# PMU.net
KiCad netlist of a schematic drawn in Altium Designer
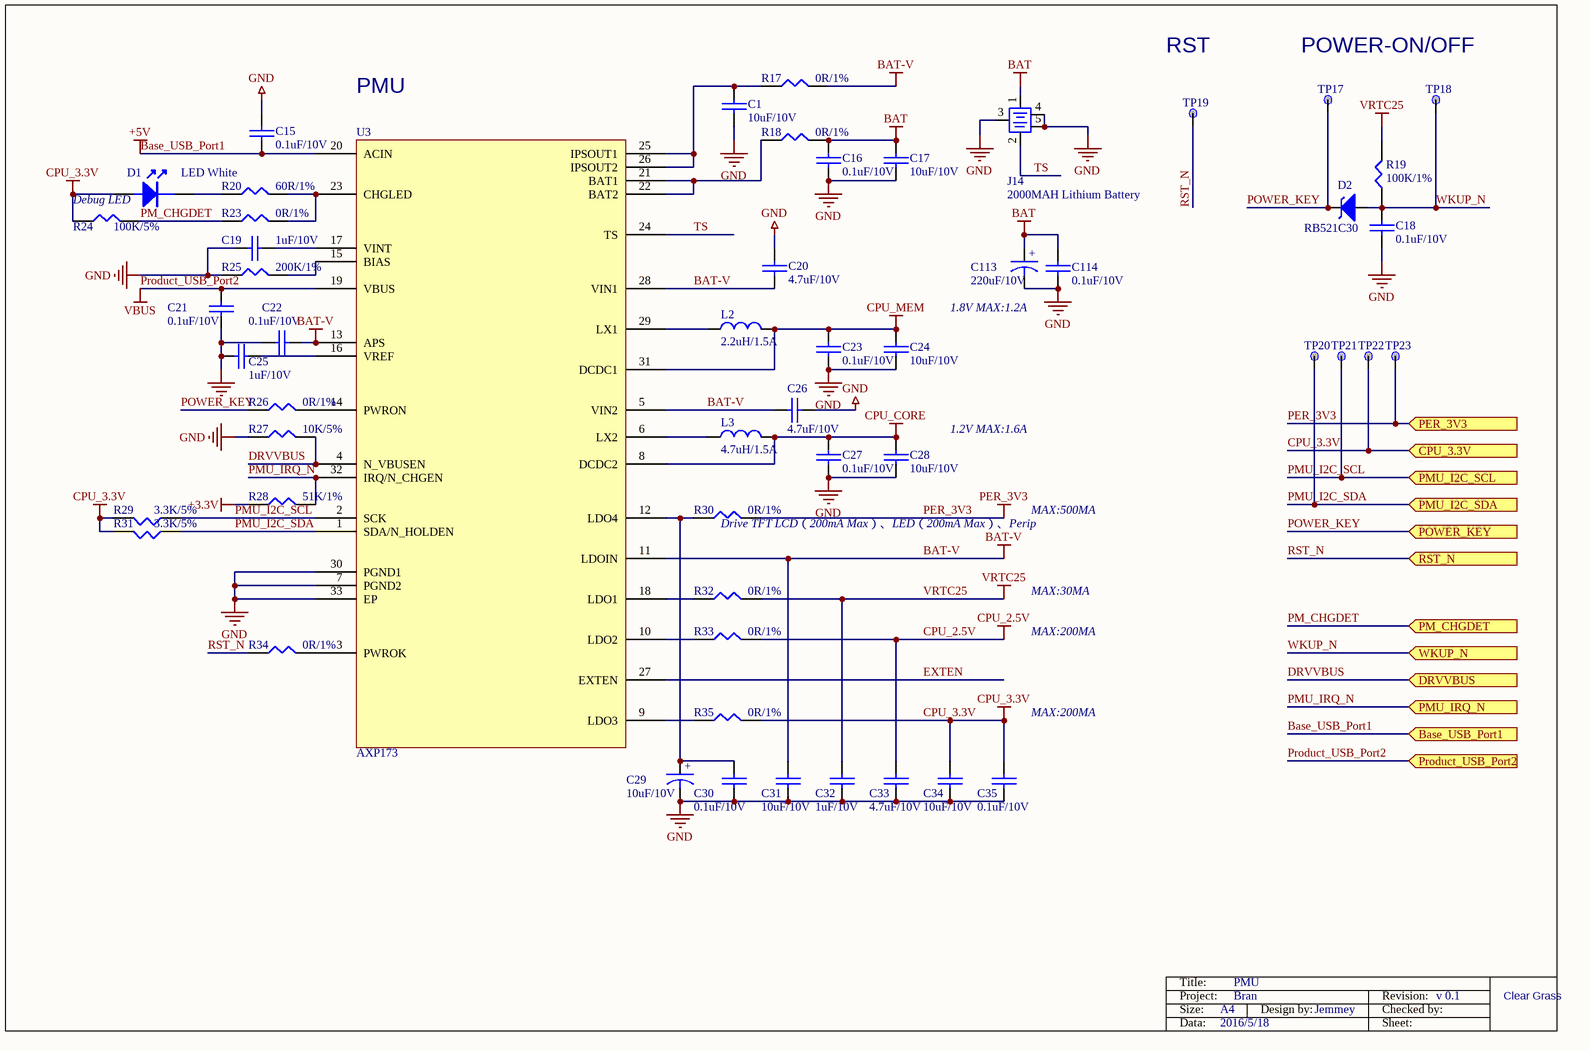
[diagram p0: PMU.SchDoc]

(export (version "E")
  (design (tool "Eeschema 10.0.6"))
  (components
    (comp (ref "C1")
      (value "10uF/10V")
      (footprint "0402C")
      (description "厂家：Murata，型号：GRM155R71A104KA01D")
      (libsource (lib "*") (part "CAP"))
    )
    (comp (ref "C15")
      (value "0.1uF/10V")
      (footprint "0402C")
      (description "厂家：Murata，型号：GRM155R71A104KA01D")
      (libsource (lib "*") (part "CAP"))
    )
    (comp (ref "C16")
      (value "0.1uF/10V")
      (footprint "0402C")
      (description "厂家：Murata，型号：GRM155R71A104KA01D")
      (libsource (lib "*") (part "CAP"))
    )
    (comp (ref "C17")
      (value "10uF/10V")
      (footprint "0402C")
      (description "厂家：Murata，型号：GRM155R71A104KA01D")
      (libsource (lib "*") (part "CAP"))
    )
    (comp (ref "C18")
      (value "0.1uF/10V")
      (footprint "0402C")
      (description "厂家：Murata，型号：GRM155R71A104KA01D")
      (libsource (lib "*") (part "CAP"))
    )
    (comp (ref "C19")
      (value "1uF/10V")
      (footprint "0402C")
      (description "厂家：Murata，型号：GRM155R71A104KA01D")
      (libsource (lib "*") (part "CAP"))
    )
    (comp (ref "C20")
      (value "4.7uF/10V")
      (footprint "0402C")
      (description "厂家：Murata，型号：GRM155R71A104KA01D")
      (libsource (lib "*") (part "CAP"))
    )
    (comp (ref "C21")
      (value "0.1uF/10V")
      (footprint "0402C")
      (description "厂家：Murata，型号：GRM155R71A104KA01D")
      (libsource (lib "*") (part "CAP"))
    )
    (comp (ref "C22")
      (value "0.1uF/10V")
      (footprint "0402C")
      (description "厂家：Murata，型号：GRM155R71A104KA01D")
      (libsource (lib "*") (part "CAP"))
    )
    (comp (ref "C23")
      (value "0.1uF/10V")
      (footprint "0402C")
      (description "厂家：Murata，型号：GRM155R71A104KA01D")
      (libsource (lib "*") (part "CAP"))
    )
    (comp (ref "C24")
      (value "10uF/10V")
      (footprint "0402C")
      (description "厂家：Murata，型号：GRM155R71A104KA01D")
      (libsource (lib "*") (part "CAP"))
    )
    (comp (ref "C25")
      (value "1uF/10V")
      (footprint "0402C")
      (description "厂家：Murata，型号：GRM155R71A104KA01D")
      (libsource (lib "*") (part "CAP"))
    )
    (comp (ref "C26")
      (value "4.7uF/10V")
      (footprint "0402C")
      (description "厂家：Murata，型号：GRM155R71A104KA01D")
      (libsource (lib "*") (part "CAP"))
    )
    (comp (ref "C27")
      (value "0.1uF/10V")
      (footprint "0402C")
      (description "厂家：Murata，型号：GRM155R71A104KA01D")
      (libsource (lib "*") (part "CAP"))
    )
    (comp (ref "C28")
      (value "10uF/10V")
      (footprint "0402C")
      (description "厂家：Murata，型号：GRM155R71A104KA01D")
      (libsource (lib "*") (part "CAP"))
    )
    (comp (ref "C29") (value "10uF/10V") (footprint "6032") (libsource (lib "MoJi LIB") (part "Capacitor")))
    (comp (ref "C30")
      (value "0.1uF/10V")
      (footprint "0402C")
      (description "厂家：Murata，型号：GRM155R71A104KA01D")
      (libsource (lib "*") (part "CAP"))
    )
    (comp (ref "C31")
      (value "10uF/10V")
      (footprint "0402C")
      (description "厂家：Murata，型号：GRM155R71A104KA01D")
      (libsource (lib "*") (part "CAP"))
    )
    (comp (ref "C32")
      (value "1uF/10V")
      (footprint "0402C")
      (description "厂家：Murata，型号：GRM155R71A104KA01D")
      (libsource (lib "*") (part "CAP"))
    )
    (comp (ref "C33")
      (value "4.7uF/10V")
      (footprint "0402C")
      (description "厂家：Murata，型号：GRM155R71A104KA01D")
      (libsource (lib "*") (part "CAP"))
    )
    (comp (ref "C34")
      (value "10uF/10V")
      (footprint "0402C")
      (description "厂家：Murata，型号：GRM155R71A104KA01D")
      (libsource (lib "*") (part "CAP"))
    )
    (comp (ref "C35")
      (value "0.1uF/10V")
      (footprint "0402C")
      (description "厂家：Murata，型号：GRM155R71A104KA01D")
      (libsource (lib "*") (part "CAP"))
    )
    (comp (ref "C113") (value "220uF/10V") (footprint "6032") (libsource (lib "MoJi LIB") (part "Capacitor")))
    (comp (ref "C114")
      (value "0.1uF/10V")
      (footprint "0402C")
      (description "厂家：Murata，型号：GRM155R71A104KA01D")
      (libsource (lib "Amber") (part "CAP"))
    )
    (comp (ref "D1")
      (value "LED White")
      (footprint "0402LED")
      (description "厂家：ROHM，型号：SCMP13WBC8W1**")
      (libsource (lib "Schlib1") (part "LED"))
    )
    (comp (ref "D2")
      (value "RB521C30")
      (footprint "DO-214AC")
      (description "厂家：ROHM，型号：RB480Y-90")
      (libsource (lib "Moji_Assenbly Test") (part "Schottky barrier rectifier"))
    )
    (comp (ref "J14")
      (value "2000MAH Lithium Battery")
      (footprint "Molex-1-3A")
      (libsource (lib "Centrol Control Panel(20141126)") (part "BL-5C"))
    )
    (comp (ref "L2") (value "2.2uH/1.5A") (footprint "Inductance") (libsource (lib "*") (part "CHOKE")))
    (comp (ref "L3") (value "4.7uH/1.5A") (footprint "Inductance") (libsource (lib "*") (part "CHOKE")))
    (comp (ref "R17")
      (value "0R/1%")
      (footprint "0402R")
      (description "厂家：Yageo，型号：RC0402FR-0710KL")
      (libsource (lib "*") (part "RES1"))
    )
    (comp (ref "R18")
      (value "0R/1%")
      (footprint "0402R")
      (description "厂家：Yageo，型号：RC0402FR-0710KL")
      (libsource (lib "*") (part "RES1"))
    )
    (comp (ref "R19")
      (value "100K/1%")
      (footprint "0402R")
      (description "厂家：Yageo，型号：RC0402FR-0710KL")
      (libsource (lib "*") (part "RES1"))
    )
    (comp (ref "R20")
      (value "60R/1%")
      (footprint "0402R")
      (description "厂家：Yageo，型号：RC0402FR-0710KL")
      (libsource (lib "*") (part "RES1"))
    )
    (comp (ref "R23")
      (value "0R/1%")
      (footprint "0402R")
      (description "厂家：Yageo，型号：RC0402FR-0710KL")
      (libsource (lib "*") (part "RES1"))
    )
    (comp (ref "R24")
      (value "100K/5%")
      (footprint "0402R")
      (description "厂家：Yageo，型号：RC0402FR-0710KL")
      (libsource (lib "*") (part "RES1"))
    )
    (comp (ref "R25")
      (value "200K/1%")
      (footprint "0402R")
      (description "厂家：Yageo，型号：RC0402FR-0710KL")
      (libsource (lib "*") (part "RES1"))
    )
    (comp (ref "R26")
      (value "0R/1%")
      (footprint "0402R")
      (description "厂家：Yageo，型号：RC0402FR-0710KL")
      (libsource (lib "*") (part "RES1"))
    )
    (comp (ref "R27")
      (value "10K/5%")
      (footprint "0402R")
      (description "厂家：Yageo，型号：RC0402FR-0710KL")
      (libsource (lib "*") (part "RES1"))
    )
    (comp (ref "R28")
      (value "51K/1%")
      (footprint "0402R")
      (description "厂家：Yageo，型号：RC0402FR-0710KL")
      (libsource (lib "*") (part "RES1"))
    )
    (comp (ref "R29")
      (value "3.3K/5%")
      (footprint "0402R")
      (description "厂家：Yageo，型号：RC0402FR-0710KL")
      (libsource (lib "*") (part "RES1"))
    )
    (comp (ref "R30")
      (value "0R/1%")
      (footprint "0402R")
      (description "厂家：Yageo，型号：RC0402FR-0710KL")
      (libsource (lib "*") (part "RES1"))
    )
    (comp (ref "R31")
      (value "3.3K/5%")
      (footprint "0402R")
      (description "厂家：Yageo，型号：RC0402FR-0710KL")
      (libsource (lib "*") (part "RES1"))
    )
    (comp (ref "R32")
      (value "0R/1%")
      (footprint "0402R")
      (description "厂家：Yageo，型号：RC0402FR-0710KL")
      (libsource (lib "*") (part "RES1"))
    )
    (comp (ref "R33")
      (value "0R/1%")
      (footprint "0402R")
      (description "厂家：Yageo，型号：RC0402FR-0710KL")
      (libsource (lib "*") (part "RES1"))
    )
    (comp (ref "R34")
      (value "0R/1%")
      (footprint "0402R")
      (description "厂家：Yageo，型号：RC0402FR-0710KL")
      (libsource (lib "*") (part "RES1"))
    )
    (comp (ref "R35")
      (value "0R/1%")
      (footprint "0402R")
      (description "厂家：Yageo，型号：RC0402FR-0710KL")
      (libsource (lib "*") (part "RES1"))
    )
    (comp (ref "TP17") (value "TP") (footprint "TP_C40") (libsource (lib "Almos") (part "TP")))
    (comp (ref "TP18") (value "TP") (footprint "TP_C40") (libsource (lib "Almos") (part "TP")))
    (comp (ref "TP19") (value "TP") (footprint "TP_C40") (libsource (lib "Almos") (part "TP")))
    (comp (ref "TP20") (value "TP") (footprint "TP_C40") (libsource (lib "Almos") (part "TP")))
    (comp (ref "TP21") (value "TP") (footprint "TP_C40") (libsource (lib "Almos") (part "TP")))
    (comp (ref "TP22") (value "TP") (footprint "TP_C40") (libsource (lib "Almos") (part "TP")))
    (comp (ref "TP23") (value "TP") (footprint "TP_C40") (libsource (lib "Almos") (part "TP")))
    (comp (ref "U3") (value "AXP173") (libsource (lib "M150") (part "AXP173")))
  )
  (nets
    (net (code "1") (name "+3.3V") (class "Default")
      (node (ref "R28") (pin "1") (pinfunction "1_1") (pintype "passive"))
    )
    (net (code "2") (name "+5V") (class "Default")
      (node (ref "C15") (pin "1") (pinfunction "1_1") (pintype "passive"))
      (node (ref "U3") (pin "20") (pinfunction "ACIN_20") (pintype "passive"))
    )
    (net (code "3") (name "/DRVVBUS") (class "Default")
      (node (ref "R27") (pin "2") (pinfunction "2_2") (pintype "passive"))
      (node (ref "U3") (pin "4") (pinfunction "N_VBUSEN_4") (pintype "passive"))
    )
    (net (code "4") (name "/EXTEN") (class "Default")
      (node (ref "U3") (pin "27") (pinfunction "EXTEN_27") (pintype "passive"))
    )
    (net (code "5") (name "/PMU_I2C_SCL") (class "Default")
      (node (ref "R29") (pin "1") (pinfunction "1_1") (pintype "passive"))
      (node (ref "TP21") (pin "1") (pinfunction "1_1") (pintype "passive"))
      (node (ref "U3") (pin "2") (pinfunction "SCK_2") (pintype "passive"))
    )
    (net (code "6") (name "/PMU_I2C_SDA") (class "Default")
      (node (ref "R31") (pin "1") (pinfunction "1_1") (pintype "passive"))
      (node (ref "TP20") (pin "1") (pinfunction "1_1") (pintype "passive"))
      (node (ref "U3") (pin "1") (pinfunction "SDA/N_HOLDEN_1") (pintype "passive"))
    )
    (net (code "7") (name "/PMU_IRQ_N") (class "Default")
      (node (ref "R28") (pin "2") (pinfunction "2_2") (pintype "passive"))
      (node (ref "U3") (pin "32") (pinfunction "IRQ/N_CHGEN_32") (pintype "passive"))
    )
    (net (code "8") (name "/PM_CHGDET") (class "Default")
      (node (ref "R23") (pin "1") (pinfunction "1_1") (pintype "passive"))
      (node (ref "R24") (pin "2") (pinfunction "2_2") (pintype "passive"))
    )
    (net (code "9") (name "/POWER_KEY") (class "Default")
      (node (ref "D2") (pin "1") (pinfunction "K_1") (pintype "passive"))
      (node (ref "R26") (pin "1") (pinfunction "1_1") (pintype "passive"))
      (node (ref "TP17") (pin "1") (pinfunction "1_1") (pintype "passive"))
    )
    (net (code "10") (name "/RST_N") (class "Default")
      (node (ref "R34") (pin "1") (pinfunction "1_1") (pintype "passive"))
      (node (ref "TP19") (pin "1") (pinfunction "1_1") (pintype "passive"))
    )
    (net (code "11") (name "/TS") (class "Default")
      (node (ref "J14") (pin "2") (pinfunction "NTC_2") (pintype "passive"))
      (node (ref "U3") (pin "24") (pinfunction "TS_24") (pintype "passive"))
    )
    (net (code "12") (name "/WKUP_N") (class "Default")
      (node (ref "C18") (pin "2") (pinfunction "2_2") (pintype "passive"))
      (node (ref "D2") (pin "2") (pinfunction "A_2") (pintype "passive"))
      (node (ref "R19") (pin "1") (pinfunction "1_1") (pintype "passive"))
      (node (ref "TP18") (pin "1") (pinfunction "1_1") (pintype "passive"))
    )
    (net (code "13") (name "BAT") (class "Default")
      (node (ref "C113") (pin "1") (pinfunction "1_1") (pintype "passive"))
      (node (ref "C114") (pin "2") (pinfunction "2_2") (pintype "passive"))
      (node (ref "C16") (pin "2") (pinfunction "2_2") (pintype "passive"))
      (node (ref "C17") (pin "2") (pinfunction "2_2") (pintype "passive"))
      (node (ref "J14") (pin "1") (pinfunction "VCC_1") (pintype "passive"))
      (node (ref "R18") (pin "2") (pinfunction "2_2") (pintype "passive"))
    )
    (net (code "14") (name "BAT-V") (class "Default")
      (node (ref "C20") (pin "2") (pinfunction "2_2") (pintype "passive"))
      (node (ref "C22") (pin "1") (pinfunction "1_1") (pintype "passive"))
      (node (ref "C26") (pin "2") (pinfunction "2_2") (pintype "passive"))
      (node (ref "C31") (pin "1") (pinfunction "1_1") (pintype "passive"))
      (node (ref "R17") (pin "2") (pinfunction "2_2") (pintype "passive"))
      (node (ref "U3") (pin "11") (pinfunction "LDOIN_11") (pintype "passive"))
      (node (ref "U3") (pin "13") (pinfunction "APS_13") (pintype "passive"))
      (node (ref "U3") (pin "28") (pinfunction "VIN1_28") (pintype "passive"))
      (node (ref "U3") (pin "5") (pinfunction "VIN2_5") (pintype "passive"))
    )
    (net (code "15") (name "CPU_2.5V") (class "Default")
      (node (ref "C33") (pin "1") (pinfunction "1_1") (pintype "passive"))
      (node (ref "R33") (pin "2") (pinfunction "2_2") (pintype "passive"))
    )
    (net (code "16") (name "CPU_3.3V") (class "Default")
      (node (ref "C34") (pin "1") (pinfunction "1_1") (pintype "passive"))
      (node (ref "C35") (pin "1") (pinfunction "1_1") (pintype "passive"))
      (node (ref "D1") (pin "2") (pinfunction "2_2") (pintype "passive"))
      (node (ref "R24") (pin "1") (pinfunction "1_1") (pintype "passive"))
      (node (ref "R29") (pin "2") (pinfunction "2_2") (pintype "passive"))
      (node (ref "R31") (pin "2") (pinfunction "2_2") (pintype "passive"))
      (node (ref "R35") (pin "2") (pinfunction "2_2") (pintype "passive"))
      (node (ref "TP22") (pin "1") (pinfunction "1_1") (pintype "passive"))
    )
    (net (code "17") (name "CPU_CORE") (class "Default")
      (node (ref "C27") (pin "2") (pinfunction "2_2") (pintype "passive"))
      (node (ref "C28") (pin "2") (pinfunction "2_2") (pintype "passive"))
      (node (ref "L3") (pin "2") (pinfunction "2_2") (pintype "passive"))
      (node (ref "U3") (pin "8") (pinfunction "DCDC2_8") (pintype "passive"))
    )
    (net (code "18") (name "CPU_MEM") (class "Default")
      (node (ref "C23") (pin "2") (pinfunction "2_2") (pintype "passive"))
      (node (ref "C24") (pin "2") (pinfunction "2_2") (pintype "passive"))
      (node (ref "L2") (pin "2") (pinfunction "2_2") (pintype "passive"))
      (node (ref "U3") (pin "31") (pinfunction "DCDC1_31") (pintype "passive"))
    )
    (net (code "19") (name "GND") (class "Default")
      (node (ref "C1") (pin "1") (pinfunction "1_1") (pintype "passive"))
      (node (ref "C113") (pin "2") (pinfunction "2_2") (pintype "passive"))
      (node (ref "C114") (pin "1") (pinfunction "1_1") (pintype "passive"))
      (node (ref "C15") (pin "2") (pinfunction "2_2") (pintype "passive"))
      (node (ref "C16") (pin "1") (pinfunction "1_1") (pintype "passive"))
      (node (ref "C17") (pin "1") (pinfunction "1_1") (pintype "passive"))
      (node (ref "C18") (pin "1") (pinfunction "1_1") (pintype "passive"))
      (node (ref "C19") (pin "2") (pinfunction "2_2") (pintype "passive"))
      (node (ref "C20") (pin "1") (pinfunction "1_1") (pintype "passive"))
      (node (ref "C21") (pin "1") (pinfunction "1_1") (pintype "passive"))
      (node (ref "C22") (pin "2") (pinfunction "2_2") (pintype "passive"))
      (node (ref "C23") (pin "1") (pinfunction "1_1") (pintype "passive"))
      (node (ref "C24") (pin "1") (pinfunction "1_1") (pintype "passive"))
      (node (ref "C25") (pin "2") (pinfunction "2_2") (pintype "passive"))
      (node (ref "C26") (pin "1") (pinfunction "1_1") (pintype "passive"))
      (node (ref "C27") (pin "1") (pinfunction "1_1") (pintype "passive"))
      (node (ref "C28") (pin "1") (pinfunction "1_1") (pintype "passive"))
      (node (ref "C29") (pin "2") (pinfunction "2_2") (pintype "passive"))
      (node (ref "C30") (pin "1") (pinfunction "1_1") (pintype "passive"))
      (node (ref "C31") (pin "2") (pinfunction "2_2") (pintype "passive"))
      (node (ref "C32") (pin "2") (pinfunction "2_2") (pintype "passive"))
      (node (ref "C33") (pin "2") (pinfunction "2_2") (pintype "passive"))
      (node (ref "C34") (pin "2") (pinfunction "2_2") (pintype "passive"))
      (node (ref "C35") (pin "2") (pinfunction "2_2") (pintype "passive"))
      (node (ref "J14") (pin "3") (pinfunction "GND_3") (pintype "passive"))
      (node (ref "J14") (pin "4") (pinfunction "PAD_4") (pintype "passive"))
      (node (ref "J14") (pin "5") (pinfunction "PAD_5") (pintype "passive"))
      (node (ref "R25") (pin "1") (pinfunction "1_1") (pintype "passive"))
      (node (ref "R27") (pin "1") (pinfunction "1_1") (pintype "passive"))
      (node (ref "U3") (pin "30") (pinfunction "PGND1_30") (pintype "passive"))
      (node (ref "U3") (pin "33") (pinfunction "EP_33") (pintype "passive"))
      (node (ref "U3") (pin "7") (pinfunction "PGND2_7") (pintype "passive"))
    )
    (net (code "20") (name "Net-(D1-Pad1)") (class "Default")
      (node (ref "D1") (pin "1") (pinfunction "1_1") (pintype "passive"))
      (node (ref "R20") (pin "1") (pinfunction "1_1") (pintype "passive"))
    )
    (net (code "21") (name "Net-(U3-BAT1)") (class "Default")
      (node (ref "R18") (pin "1") (pinfunction "1_1") (pintype "passive"))
      (node (ref "U3") (pin "21") (pinfunction "BAT1_21") (pintype "passive"))
      (node (ref "U3") (pin "22") (pinfunction "BAT2_22") (pintype "passive"))
    )
    (net (code "22") (name "Net-(U3-BIAS)") (class "Default")
      (node (ref "R25") (pin "2") (pinfunction "2_2") (pintype "passive"))
      (node (ref "U3") (pin "15") (pinfunction "BIAS_15") (pintype "passive"))
    )
    (net (code "23") (name "Net-(U3-CHGLED)") (class "Default")
      (node (ref "R20") (pin "2") (pinfunction "2_2") (pintype "passive"))
      (node (ref "R23") (pin "2") (pinfunction "2_2") (pintype "passive"))
      (node (ref "U3") (pin "23") (pinfunction "CHGLED_23") (pintype "passive"))
    )
    (net (code "24") (name "Net-(U3-IPSOUT1)") (class "Default")
      (node (ref "C1") (pin "2") (pinfunction "2_2") (pintype "passive"))
      (node (ref "R17") (pin "1") (pinfunction "1_1") (pintype "passive"))
      (node (ref "U3") (pin "25") (pinfunction "IPSOUT1_25") (pintype "passive"))
      (node (ref "U3") (pin "26") (pinfunction "IPSOUT2_26") (pintype "passive"))
    )
    (net (code "25") (name "Net-(U3-LDO1)") (class "Default")
      (node (ref "R32") (pin "1") (pinfunction "1_1") (pintype "passive"))
      (node (ref "U3") (pin "18") (pinfunction "LDO1_18") (pintype "passive"))
    )
    (net (code "26") (name "Net-(U3-LDO2)") (class "Default")
      (node (ref "R33") (pin "1") (pinfunction "1_1") (pintype "passive"))
      (node (ref "U3") (pin "10") (pinfunction "LDO2_10") (pintype "passive"))
    )
    (net (code "27") (name "Net-(U3-LDO3)") (class "Default")
      (node (ref "R35") (pin "1") (pinfunction "1_1") (pintype "passive"))
      (node (ref "U3") (pin "9") (pinfunction "LDO3_9") (pintype "passive"))
    )
    (net (code "28") (name "Net-(U3-LDO4)") (class "Default")
      (node (ref "C29") (pin "1") (pinfunction "1_1") (pintype "passive"))
      (node (ref "C30") (pin "2") (pinfunction "2_2") (pintype "passive"))
      (node (ref "R30") (pin "1") (pinfunction "1_1") (pintype "passive"))
      (node (ref "U3") (pin "12") (pinfunction "LDO4_12") (pintype "passive"))
    )
    (net (code "29") (name "Net-(U3-LX1)") (class "Default")
      (node (ref "L2") (pin "1") (pinfunction "1_1") (pintype "passive"))
      (node (ref "U3") (pin "29") (pinfunction "LX1_29") (pintype "passive"))
    )
    (net (code "30") (name "Net-(U3-LX2)") (class "Default")
      (node (ref "L3") (pin "1") (pinfunction "1_1") (pintype "passive"))
      (node (ref "U3") (pin "6") (pinfunction "LX2_6") (pintype "passive"))
    )
    (net (code "31") (name "Net-(U3-PWROK)") (class "Default")
      (node (ref "R34") (pin "2") (pinfunction "2_2") (pintype "passive"))
      (node (ref "U3") (pin "3") (pinfunction "PWROK_3") (pintype "passive"))
    )
    (net (code "32") (name "Net-(U3-PWRON)") (class "Default")
      (node (ref "R26") (pin "2") (pinfunction "2_2") (pintype "passive"))
      (node (ref "U3") (pin "14") (pinfunction "PWRON_14") (pintype "passive"))
    )
    (net (code "33") (name "Net-(U3-VINT)") (class "Default")
      (node (ref "C19") (pin "1") (pinfunction "1_1") (pintype "passive"))
      (node (ref "U3") (pin "17") (pinfunction "VINT_17") (pintype "passive"))
    )
    (net (code "34") (name "Net-(U3-VREF)") (class "Default")
      (node (ref "C25") (pin "1") (pinfunction "1_1") (pintype "passive"))
      (node (ref "U3") (pin "16") (pinfunction "VREF_16") (pintype "passive"))
    )
    (net (code "35") (name "PER_3V3") (class "Default")
      (node (ref "R30") (pin "2") (pinfunction "2_2") (pintype "passive"))
      (node (ref "TP23") (pin "1") (pinfunction "1_1") (pintype "passive"))
    )
    (net (code "36") (name "VBUS") (class "Default")
      (node (ref "C21") (pin "2") (pinfunction "2_2") (pintype "passive"))
      (node (ref "U3") (pin "19") (pinfunction "VBUS_19") (pintype "passive"))
    )
    (net (code "37") (name "VRTC25") (class "Default")
      (node (ref "C32") (pin "1") (pinfunction "1_1") (pintype "passive"))
      (node (ref "R19") (pin "2") (pinfunction "2_2") (pintype "passive"))
      (node (ref "R32") (pin "2") (pinfunction "2_2") (pintype "passive"))
    )
  )
)
